# SCH_Linefollowerv1_2022-11-18.net
KiCad netlist of a schematic drawn in EasyEDA
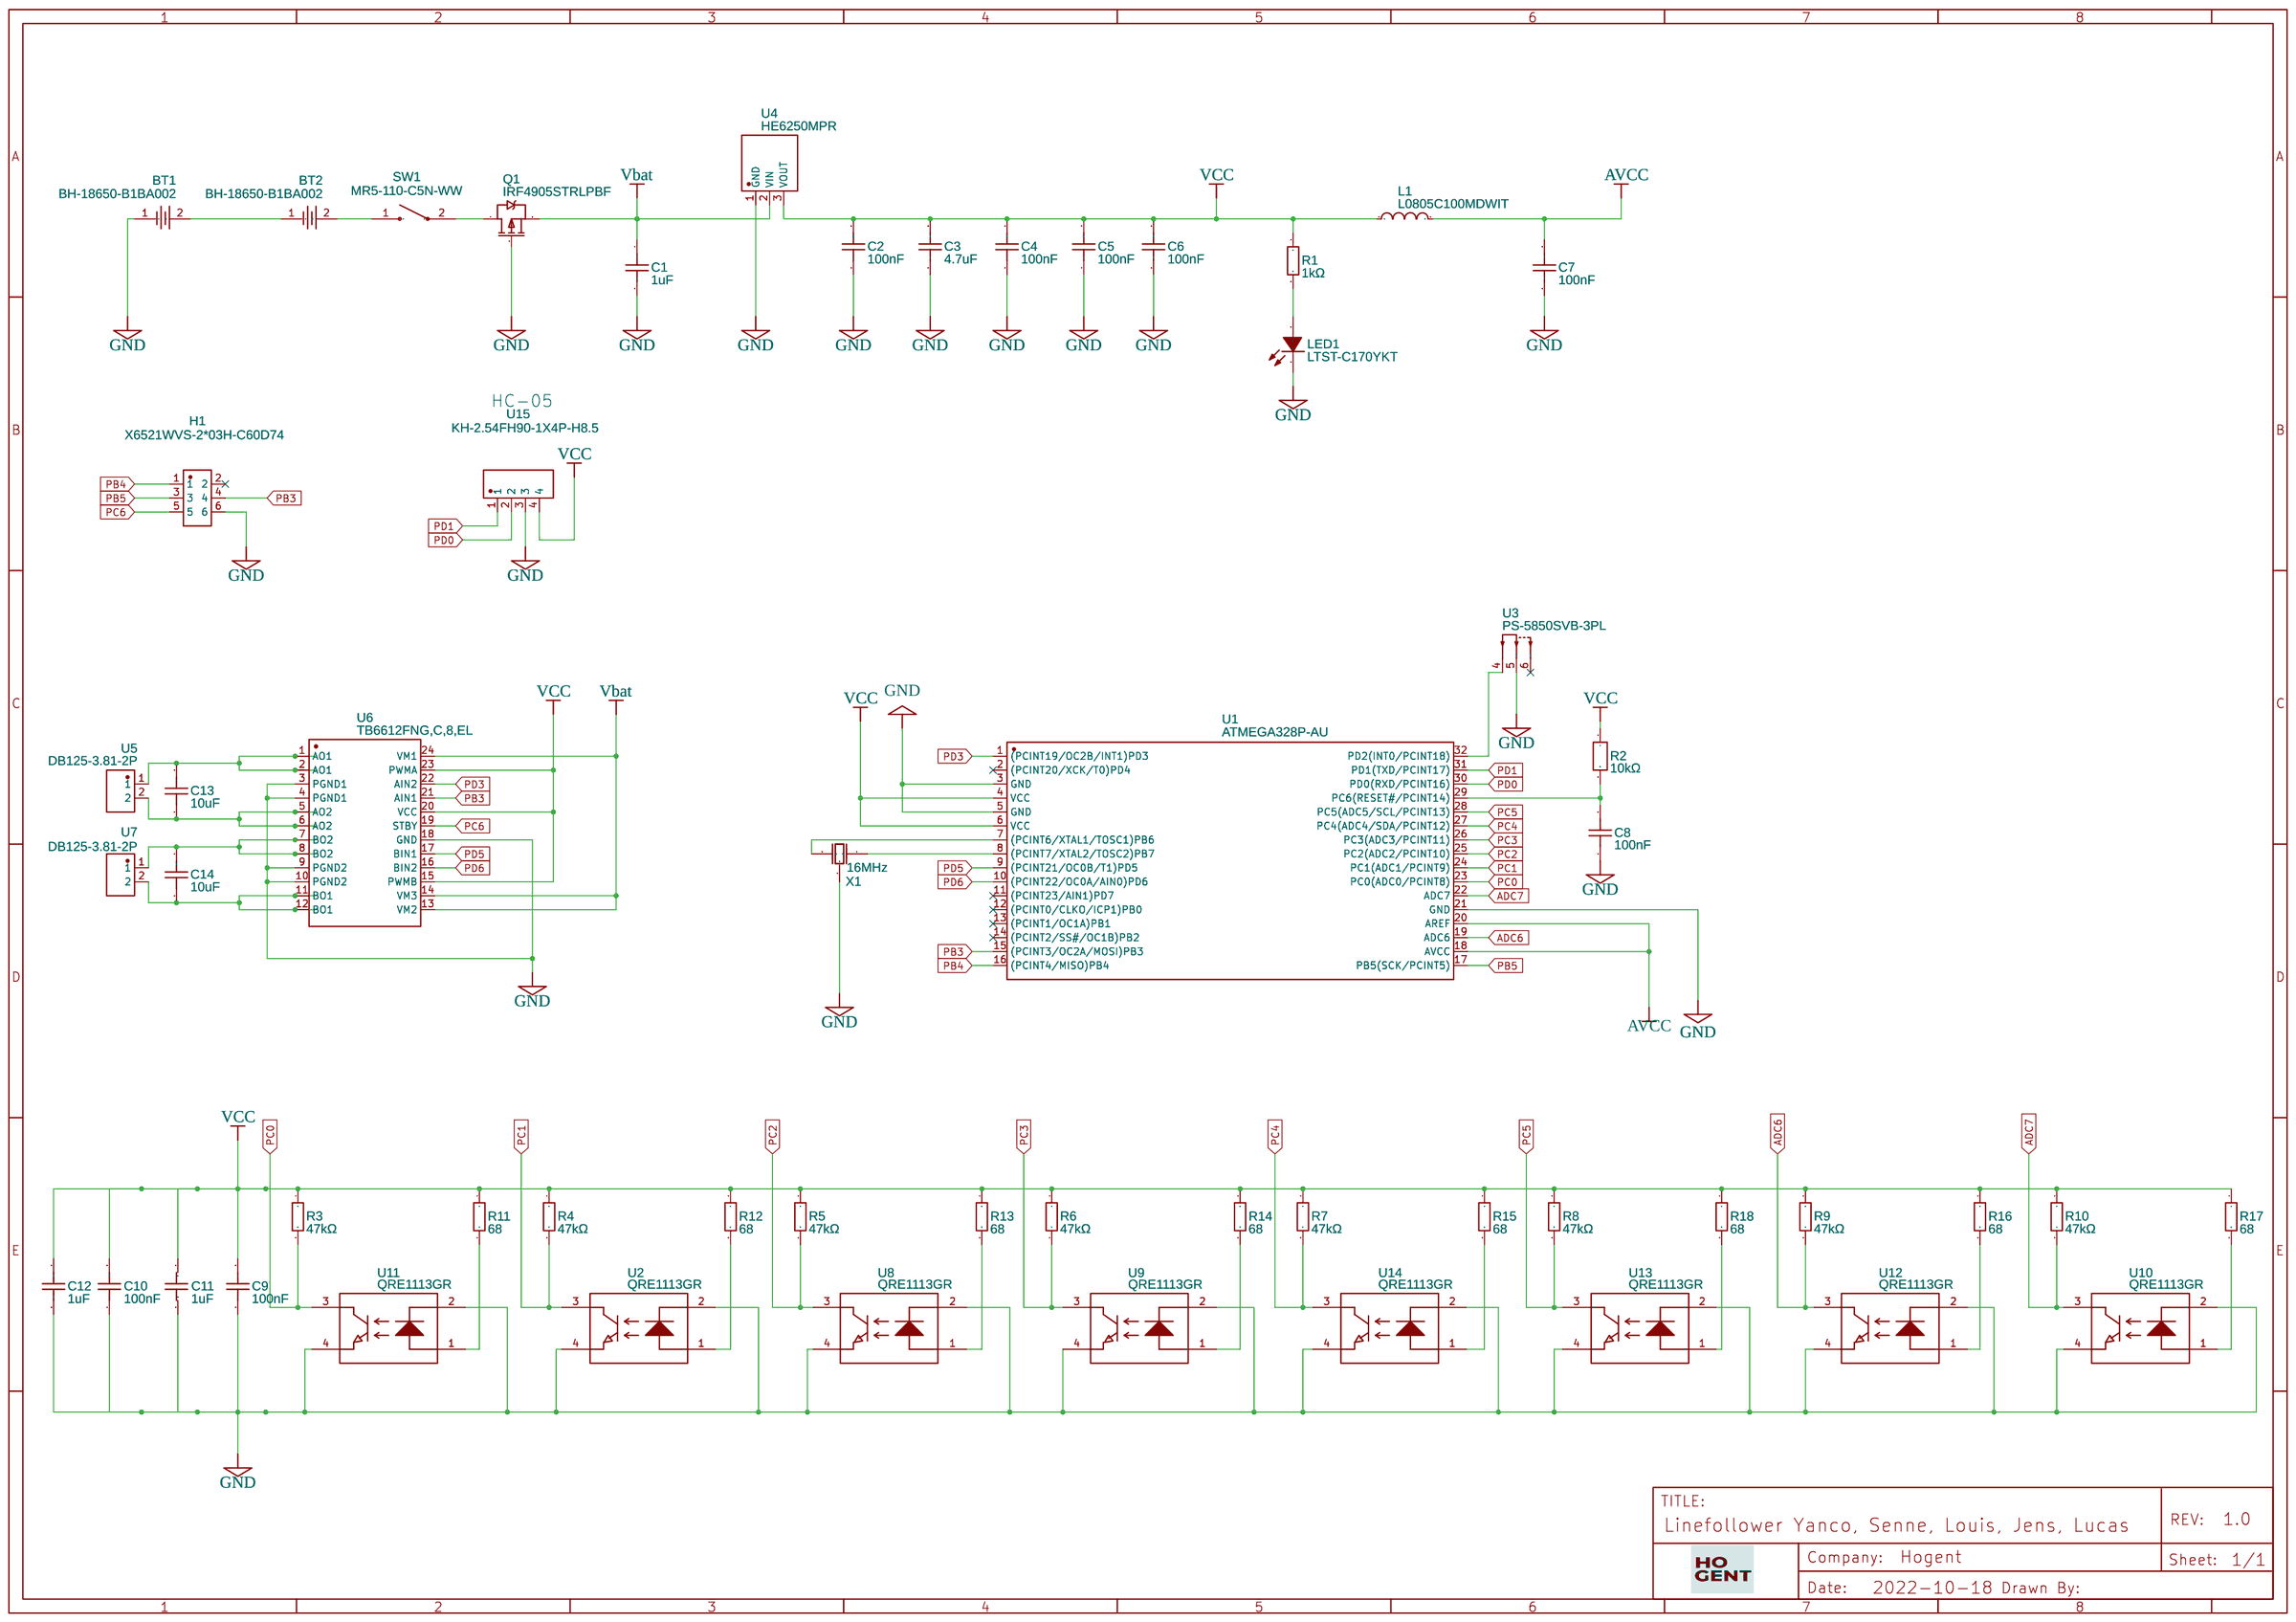
[diagram p0: schematic sheet]

(export (version "E")
  (design (tool "Eeschema 10.0.6"))
  (components
    (comp (ref "BT1")
      (value "BH-18650-B1BA002")
      (fields (field (name "BOM_Supplier Part") "C2988620"))
      (libsource (lib "") (part "BH-18650-B1BA002"))
    )
    (comp (ref "BT2")
      (value "BH-18650-B1BA002")
      (fields (field (name "BOM_Supplier Part") "C2988620"))
      (libsource (lib "") (part "BH-18650-B1BA002"))
    )
    (comp (ref "C1")
      (value "1uF")
      (fields
        (field (name "BOM_Manufacturer Part") "LMK212BJ105KD-T")
        (field (name "BOM_Supplier Part") "C92812")
      )
      (libsource (lib "") (part "LMK212BJ105KD-T_1"))
    )
    (comp (ref "C2")
      (value "100nF")
      (fields
        (field (name "BOM_Manufacturer Part") "LMK212SD104KG-T")
        (field (name "BOM_Supplier Part") "C386062")
      )
      (libsource (lib "") (part "LMK212SD104KG-T"))
    )
    (comp (ref "C3")
      (value "4.7uF")
      (fields
        (field (name "BOM_Manufacturer Part") "GCM21BC71A475KA73L")
        (field (name "BOM_Supplier Part") "C126583")
      )
      (libsource (lib "") (part "GCM21BC71A475KA73L"))
    )
    (comp (ref "C4")
      (value "100nF")
      (fields
        (field (name "BOM_Manufacturer Part") "LMK212SD104KG-T")
        (field (name "BOM_Supplier Part") "C386062")
      )
      (libsource (lib "") (part "LMK212SD104KG-T"))
    )
    (comp (ref "C5")
      (value "100nF")
      (fields
        (field (name "BOM_Manufacturer Part") "LMK212SD104KG-T")
        (field (name "BOM_Supplier Part") "C386062")
      )
      (libsource (lib "") (part "LMK212SD104KG-T"))
    )
    (comp (ref "C6")
      (value "100nF")
      (fields
        (field (name "BOM_Manufacturer Part") "LMK212SD104KG-T")
        (field (name "BOM_Supplier Part") "C386062")
      )
      (libsource (lib "") (part "LMK212SD104KG-T"))
    )
    (comp (ref "C7")
      (value "100nF")
      (fields
        (field (name "BOM_Manufacturer Part") "LMK212SD104KG-T")
        (field (name "BOM_Supplier Part") "C386062")
      )
      (libsource (lib "") (part "LMK212SD104KG-T"))
    )
    (comp (ref "C8")
      (value "100nF")
      (fields
        (field (name "BOM_Manufacturer Part") "LMK212SD104KG-T")
        (field (name "BOM_Supplier Part") "C386062")
      )
      (libsource (lib "") (part "LMK212SD104KG-T"))
    )
    (comp (ref "C9")
      (value "100nF")
      (fields
        (field (name "BOM_Manufacturer Part") "LMK212SD104KG-T")
        (field (name "BOM_Supplier Part") "C386062")
      )
      (libsource (lib "") (part "LMK212SD104KG-T"))
    )
    (comp (ref "C10")
      (value "100nF")
      (fields
        (field (name "BOM_Manufacturer Part") "LMK212SD104KG-T")
        (field (name "BOM_Supplier Part") "C386062")
      )
      (libsource (lib "") (part "LMK212SD104KG-T"))
    )
    (comp (ref "C11")
      (value "1uF")
      (fields
        (field (name "BOM_Manufacturer Part") "LMK212BJ105KD-T")
        (field (name "BOM_Supplier Part") "C92812")
      )
      (libsource (lib "") (part "LMK212BJ105KD-T"))
    )
    (comp (ref "C12")
      (value "1uF")
      (fields
        (field (name "BOM_Manufacturer Part") "LMK212BJ105KD-T")
        (field (name "BOM_Supplier Part") "C92812")
      )
      (libsource (lib "") (part "LMK212BJ105KD-T_1"))
    )
    (comp (ref "C13")
      (value "10uF")
      (fields
        (field (name "BOM_Manufacturer Part") "LMK212BJ106KD-T")
        (field (name "BOM_Supplier Part") "C89143")
      )
      (libsource (lib "") (part "LMK212BJ106KD-T"))
    )
    (comp (ref "C14")
      (value "10uF")
      (fields
        (field (name "BOM_Manufacturer Part") "LMK212BJ106KD-T")
        (field (name "BOM_Supplier Part") "C89143")
      )
      (libsource (lib "") (part "LMK212BJ106KD-T"))
    )
    (comp (ref "H1")
      (value "X6521WVS-2*03H-C60D74")
      (fields (field (name "BOM_Supplier Part") "C780054"))
      (libsource (lib "") (part "X6521WVS-2*03H-C60D74"))
    )
    (comp (ref "L1")
      (value "L0805C100MDWIT")
      (fields (field (name "BOM_Supplier Part") "C696787"))
      (libsource (lib "") (part "L0805C100MDWIT"))
    )
    (comp (ref "LED1")
      (value "LTST-C170YKT")
      (fields (field (name "BOM_Supplier Part") "C125092"))
      (libsource (lib "") (part "LTST-C170YKT"))
    )
    (comp (ref "Q1")
      (value "IRF4905STRLPBF")
      (fields (field (name "BOM_Supplier Part") "C2620"))
      (libsource (lib "") (part "IRF4905STRLPBF"))
    )
    (comp (ref "R1")
      (value "1kΩ")
      (fields
        (field (name "BOM_Manufacturer Part") "ARG05BTC1001")
        (field (name "BOM_Supplier Part") "C309081")
      )
      (libsource (lib "") (part "ARG05BTC1001"))
    )
    (comp (ref "R2")
      (value "10kΩ")
      (fields
        (field (name "BOM_Manufacturer Part") "ARG05BTC1002")
        (field (name "BOM_Supplier Part") "C406725")
      )
      (libsource (lib "") (part "ARG05BTC1002"))
    )
    (comp (ref "R3")
      (value "47kΩ")
      (fields
        (field (name "BOM_Manufacturer Part") "AECR0805F47K0K9")
        (field (name "BOM_Supplier Part") "C328397")
      )
      (libsource (lib "") (part "AECR0805F47K0K9"))
    )
    (comp (ref "R4")
      (value "47kΩ")
      (fields
        (field (name "BOM_Manufacturer Part") "AECR0805F47K0K9")
        (field (name "BOM_Supplier Part") "C328397")
      )
      (libsource (lib "") (part "AECR0805F47K0K9"))
    )
    (comp (ref "R5")
      (value "47kΩ")
      (fields
        (field (name "BOM_Manufacturer Part") "AECR0805F47K0K9")
        (field (name "BOM_Supplier Part") "C328397")
      )
      (libsource (lib "") (part "AECR0805F47K0K9"))
    )
    (comp (ref "R6")
      (value "47kΩ")
      (fields
        (field (name "BOM_Manufacturer Part") "AECR0805F47K0K9")
        (field (name "BOM_Supplier Part") "C328397")
      )
      (libsource (lib "") (part "AECR0805F47K0K9"))
    )
    (comp (ref "R7")
      (value "47kΩ")
      (fields
        (field (name "BOM_Manufacturer Part") "AECR0805F47K0K9")
        (field (name "BOM_Supplier Part") "C328397")
      )
      (libsource (lib "") (part "AECR0805F47K0K9"))
    )
    (comp (ref "R8")
      (value "47kΩ")
      (fields
        (field (name "BOM_Manufacturer Part") "AECR0805F47K0K9")
        (field (name "BOM_Supplier Part") "C328397")
      )
      (libsource (lib "") (part "AECR0805F47K0K9"))
    )
    (comp (ref "R9")
      (value "47kΩ")
      (fields
        (field (name "BOM_Manufacturer Part") "AECR0805F47K0K9")
        (field (name "BOM_Supplier Part") "C328397")
      )
      (libsource (lib "") (part "AECR0805F47K0K9"))
    )
    (comp (ref "R10")
      (value "47kΩ")
      (fields
        (field (name "BOM_Manufacturer Part") "AECR0805F47K0K9")
        (field (name "BOM_Supplier Part") "C328397")
      )
      (libsource (lib "") (part "AECR0805F47K0K9"))
    )
    (comp (ref "R11")
      (value "68")
      (fields
        (field (name "BOM_Manufacturer Part") "RC0805FR-0768RL")
        (field (name "BOM_Supplier Part") "C137498")
      )
      (libsource (lib "") (part "RC0805FR-0768RL"))
    )
    (comp (ref "R12")
      (value "68")
      (fields
        (field (name "BOM_Manufacturer Part") "RC0805FR-0768RL")
        (field (name "BOM_Supplier Part") "C137498")
      )
      (libsource (lib "") (part "RC0805FR-0768RL"))
    )
    (comp (ref "R13")
      (value "68")
      (fields
        (field (name "BOM_Manufacturer Part") "RC0805FR-0768RL")
        (field (name "BOM_Supplier Part") "C137498")
      )
      (libsource (lib "") (part "RC0805FR-0768RL"))
    )
    (comp (ref "R14")
      (value "68")
      (fields
        (field (name "BOM_Manufacturer Part") "RC0805FR-0768RL")
        (field (name "BOM_Supplier Part") "C137498")
      )
      (libsource (lib "") (part "RC0805FR-0768RL"))
    )
    (comp (ref "R15")
      (value "68")
      (fields
        (field (name "BOM_Manufacturer Part") "RC0805FR-0768RL")
        (field (name "BOM_Supplier Part") "C137498")
      )
      (libsource (lib "") (part "RC0805FR-0768RL"))
    )
    (comp (ref "R16")
      (value "68")
      (fields
        (field (name "BOM_Manufacturer Part") "RC0805FR-0768RL")
        (field (name "BOM_Supplier Part") "C137498")
      )
      (libsource (lib "") (part "RC0805FR-0768RL"))
    )
    (comp (ref "R17")
      (value "68")
      (fields
        (field (name "BOM_Manufacturer Part") "RC0805FR-0768RL")
        (field (name "BOM_Supplier Part") "C137498")
      )
      (libsource (lib "") (part "RC0805FR-0768RL"))
    )
    (comp (ref "R18")
      (value "68")
      (fields
        (field (name "BOM_Manufacturer Part") "RC0805FR-0768RL")
        (field (name "BOM_Supplier Part") "C137498")
      )
      (libsource (lib "") (part "RC0805FR-0768RL"))
    )
    (comp (ref "SW1")
      (value "MR5-110-C5N-WW")
      (fields (field (name "BOM_Supplier Part") "C2829507"))
      (libsource (lib "") (part "MR5-110-C5N-WW"))
    )
    (comp (ref "U1")
      (value "ATMEGA328P-AU")
      (fields (field (name "BOM_Supplier Part") "C14877"))
      (libsource (lib "") (part "ATMEGA328P-AU"))
    )
    (comp (ref "U2")
      (value "QRE1113GR")
      (fields (field (name "BOM_Supplier Part") "C232862"))
      (libsource (lib "") (part "QRE1113GR"))
    )
    (comp (ref "U3")
      (value "PS-5850SVB-3PL")
      (fields (field (name "BOM_Supplier Part") "C5159077"))
      (libsource (lib "") (part "PS-5850SVB-3PL"))
    )
    (comp (ref "U4")
      (value "HE6250MPR")
      (fields (field (name "BOM_Supplier Part") "C711940"))
      (libsource (lib "") (part "HE6250MPR"))
    )
    (comp (ref "U5")
      (value "DB125-3.81-2P")
      (fields (field (name "BOM_Supplier Part") "C395878"))
      (libsource (lib "") (part "DB125-3.81-2P"))
    )
    (comp (ref "U6")
      (value "TB6612FNG,C,8,EL")
      (fields (field (name "BOM_Supplier Part") "C141517"))
      (libsource (lib "") (part "Unknown_500_-570"))
    )
    (comp (ref "U7")
      (value "DB125-3.81-2P")
      (fields (field (name "BOM_Supplier Part") "C395878"))
      (libsource (lib "") (part "DB125-3.81-2P"))
    )
    (comp (ref "U8")
      (value "QRE1113GR")
      (fields (field (name "BOM_Supplier Part") "C232862"))
      (libsource (lib "") (part "QRE1113GR_4"))
    )
    (comp (ref "U9")
      (value "QRE1113GR")
      (fields (field (name "BOM_Supplier Part") "C232862"))
      (libsource (lib "") (part "QRE1113GR_2"))
    )
    (comp (ref "U10")
      (value "QRE1113GR")
      (fields (field (name "BOM_Supplier Part") "C232862"))
      (libsource (lib "") (part "QRE1113GR_6"))
    )
    (comp (ref "U11")
      (value "QRE1113GR")
      (fields (field (name "BOM_Supplier Part") "C232862"))
      (libsource (lib "") (part "QRE1113GR_6"))
    )
    (comp (ref "U12")
      (value "QRE1113GR")
      (fields (field (name "BOM_Supplier Part") "C232862"))
      (libsource (lib "") (part "QRE1113GR_5"))
    )
    (comp (ref "U13")
      (value "QRE1113GR")
      (fields (field (name "BOM_Supplier Part") "C232862"))
      (libsource (lib "") (part "QRE1113GR_1"))
    )
    (comp (ref "U14")
      (value "QRE1113GR")
      (fields (field (name "BOM_Supplier Part") "C232862"))
      (libsource (lib "") (part "QRE1113GR_3"))
    )
    (comp (ref "U15")
      (value "KH-2.54FH90-1X4P-H8.5")
      (fields (field (name "BOM_Supplier Part") "C2932680"))
      (libsource (lib "") (part "KH-2.54FH90-1X4P-H8.5"))
    )
    (comp (ref "X1")
      (value "16MHz")
      (fields
        (field (name "BOM_Manufacturer Part") "CSTNE16M0V53C000R0")
        (field (name "BOM_Supplier Part") "C882606")
      )
      (libsource (lib "") (part "CSTNE16M0V53C000R0"))
    )
  )
  (nets
    (net (code "1") (name "ADC6") (class "Default")
      (node (ref "R9") (pin "2") (pinfunction "2_2") (pintype "unspecified"))
      (node (ref "U1") (pin "19") (pinfunction "ADC6_19") (pintype "unspecified"))
      (node (ref "U12") (pin "3") (pinfunction "3_3") (pintype "input"))
    )
    (net (code "2") (name "ADC7") (class "Default")
      (node (ref "R10") (pin "2") (pinfunction "2_2") (pintype "unspecified"))
      (node (ref "U1") (pin "22") (pinfunction "ADC7_22") (pintype "unspecified"))
      (node (ref "U10") (pin "3") (pinfunction "3_3") (pintype "input"))
    )
    (net (code "3") (name "AVCC") (class "Default")
      (node (ref "C7") (pin "2") (pinfunction "2_2") (pintype "unspecified"))
      (node (ref "L1") (pin "2") (pinfunction "2_2") (pintype "unspecified"))
      (node (ref "U1") (pin "18") (pinfunction "AVCC_18") (pintype "unspecified"))
      (node (ref "U1") (pin "20") (pinfunction "AREF_20") (pintype "unspecified"))
    )
    (net (code "4") (name "GND") (class "Default")
      (node (ref "BT1") (pin "1") (pinfunction "1_1") (pintype "input"))
      (node (ref "C1") (pin "2") (pinfunction "2_2") (pintype "unspecified"))
      (node (ref "C10") (pin "1") (pinfunction "1_1") (pintype "unspecified"))
      (node (ref "C11") (pin "2") (pinfunction "2_2") (pintype "unspecified"))
      (node (ref "C12") (pin "2") (pinfunction "2_2") (pintype "unspecified"))
      (node (ref "C2") (pin "1") (pinfunction "1_1") (pintype "unspecified"))
      (node (ref "C3") (pin "1") (pinfunction "1_1") (pintype "unspecified"))
      (node (ref "C4") (pin "1") (pinfunction "1_1") (pintype "unspecified"))
      (node (ref "C5") (pin "1") (pinfunction "1_1") (pintype "unspecified"))
      (node (ref "C6") (pin "1") (pinfunction "1_1") (pintype "unspecified"))
      (node (ref "C7") (pin "1") (pinfunction "1_1") (pintype "unspecified"))
      (node (ref "C8") (pin "1") (pinfunction "1_1") (pintype "unspecified"))
      (node (ref "C9") (pin "1") (pinfunction "1_1") (pintype "unspecified"))
      (node (ref "H1") (pin "6") (pinfunction "6_6") (pintype "unspecified"))
      (node (ref "LED1") (pin "1") (pinfunction "1_1") (pintype "unspecified"))
      (node (ref "Q1") (pin "1") (pinfunction "G_1") (pintype "unspecified"))
      (node (ref "U1") (pin "21") (pinfunction "GND_21") (pintype "unspecified"))
      (node (ref "U1") (pin "3") (pinfunction "GND_3") (pintype "unspecified"))
      (node (ref "U1") (pin "5") (pinfunction "GND_5") (pintype "unspecified"))
      (node (ref "U10") (pin "2") (pinfunction "2_2") (pintype "input"))
      (node (ref "U10") (pin "4") (pinfunction "4_4") (pintype "input"))
      (node (ref "U11") (pin "2") (pinfunction "2_2") (pintype "input"))
      (node (ref "U11") (pin "4") (pinfunction "4_4") (pintype "input"))
      (node (ref "U12") (pin "2") (pinfunction "2_2") (pintype "input"))
      (node (ref "U12") (pin "4") (pinfunction "4_4") (pintype "input"))
      (node (ref "U13") (pin "2") (pinfunction "2_2") (pintype "input"))
      (node (ref "U13") (pin "4") (pinfunction "4_4") (pintype "input"))
      (node (ref "U14") (pin "2") (pinfunction "2_2") (pintype "input"))
      (node (ref "U14") (pin "4") (pinfunction "4_4") (pintype "input"))
      (node (ref "U15") (pin "3") (pinfunction "3_3") (pintype "unspecified"))
      (node (ref "U2") (pin "2") (pinfunction "2_2") (pintype "input"))
      (node (ref "U2") (pin "4") (pinfunction "4_4") (pintype "input"))
      (node (ref "U3") (pin "5") (pinfunction "5_5") (pintype "unspecified"))
      (node (ref "U4") (pin "1") (pinfunction "GND_1") (pintype "unspecified"))
      (node (ref "U6") (pin "10") (pinfunction "PGND2_10") (pintype "unspecified"))
      (node (ref "U6") (pin "18") (pinfunction "GND_18") (pintype "unspecified"))
      (node (ref "U6") (pin "3") (pinfunction "PGND1_3") (pintype "unspecified"))
      (node (ref "U6") (pin "4") (pinfunction "PGND1_4") (pintype "unspecified"))
      (node (ref "U6") (pin "9") (pinfunction "PGND2_9") (pintype "unspecified"))
      (node (ref "U8") (pin "2") (pinfunction "2_2") (pintype "input"))
      (node (ref "U8") (pin "4") (pinfunction "4_4") (pintype "input"))
      (node (ref "U9") (pin "2") (pinfunction "2_2") (pintype "input"))
      (node (ref "U9") (pin "4") (pinfunction "4_4") (pintype "input"))
      (node (ref "X1") (pin "2") (pinfunction "GND_2") (pintype "input"))
    )
    (net (code "5") (name "Net-(BT1-Pad2)") (class "Default")
      (node (ref "BT1") (pin "2") (pinfunction "2_2") (pintype "input"))
      (node (ref "BT2") (pin "1") (pinfunction "1_1") (pintype "input"))
    )
    (net (code "6") (name "Net-(BT2-Pad2)") (class "Default")
      (node (ref "BT2") (pin "2") (pinfunction "2_2") (pintype "input"))
      (node (ref "SW1") (pin "1") (pinfunction "1_1") (pintype "unspecified"))
    )
    (net (code "7") (name "Net-(C13-Pad1)") (class "Default")
      (node (ref "C13") (pin "1") (pinfunction "1_1") (pintype "unspecified"))
      (node (ref "U5") (pin "2") (pinfunction "2_2") (pintype "unspecified"))
      (node (ref "U6") (pin "5") (pinfunction "AO2_5") (pintype "unspecified"))
      (node (ref "U6") (pin "6") (pinfunction "AO2_6") (pintype "unspecified"))
    )
    (net (code "8") (name "Net-(C13-Pad2)") (class "Default")
      (node (ref "C13") (pin "2") (pinfunction "2_2") (pintype "unspecified"))
      (node (ref "U5") (pin "1") (pinfunction "1_1") (pintype "unspecified"))
      (node (ref "U6") (pin "1") (pinfunction "AO1_1") (pintype "unspecified"))
      (node (ref "U6") (pin "2") (pinfunction "AO1_2") (pintype "unspecified"))
    )
    (net (code "9") (name "Net-(C14-Pad1)") (class "Default")
      (node (ref "C14") (pin "1") (pinfunction "1_1") (pintype "unspecified"))
      (node (ref "U6") (pin "11") (pinfunction "BO1_11") (pintype "unspecified"))
      (node (ref "U6") (pin "12") (pinfunction "BO1_12") (pintype "unspecified"))
      (node (ref "U7") (pin "2") (pinfunction "2_2") (pintype "unspecified"))
    )
    (net (code "10") (name "Net-(C14-Pad2)") (class "Default")
      (node (ref "C14") (pin "2") (pinfunction "2_2") (pintype "unspecified"))
      (node (ref "U6") (pin "7") (pinfunction "BO2_7") (pintype "unspecified"))
      (node (ref "U6") (pin "8") (pinfunction "BO2_8") (pintype "unspecified"))
      (node (ref "U7") (pin "1") (pinfunction "1_1") (pintype "unspecified"))
    )
    (net (code "11") (name "Net-(LED1-Pad2)") (class "Default")
      (node (ref "LED1") (pin "2") (pinfunction "2_2") (pintype "unspecified"))
      (node (ref "R1") (pin "2") (pinfunction "2_2") (pintype "unspecified"))
    )
    (net (code "12") (name "Net-(Q1-D)") (class "Default")
      (node (ref "Q1") (pin "4") (pinfunction "D_4") (pintype "unspecified"))
      (node (ref "SW1") (pin "2") (pinfunction "2_2") (pintype "unspecified"))
    )
    (net (code "13") (name "Net-(R11-Pad2)") (class "Default")
      (node (ref "R11") (pin "2") (pinfunction "2_2") (pintype "input"))
      (node (ref "U11") (pin "1") (pinfunction "1_1") (pintype "input"))
    )
    (net (code "14") (name "Net-(R12-Pad2)") (class "Default")
      (node (ref "R12") (pin "2") (pinfunction "2_2") (pintype "input"))
      (node (ref "U2") (pin "1") (pinfunction "1_1") (pintype "input"))
    )
    (net (code "15") (name "Net-(R13-Pad2)") (class "Default")
      (node (ref "R13") (pin "2") (pinfunction "2_2") (pintype "input"))
      (node (ref "U8") (pin "1") (pinfunction "1_1") (pintype "input"))
    )
    (net (code "16") (name "Net-(R14-Pad2)") (class "Default")
      (node (ref "R14") (pin "2") (pinfunction "2_2") (pintype "input"))
      (node (ref "U9") (pin "1") (pinfunction "1_1") (pintype "input"))
    )
    (net (code "17") (name "Net-(R15-Pad2)") (class "Default")
      (node (ref "R15") (pin "2") (pinfunction "2_2") (pintype "input"))
      (node (ref "U14") (pin "1") (pinfunction "1_1") (pintype "input"))
    )
    (net (code "18") (name "Net-(R16-Pad2)") (class "Default")
      (node (ref "R16") (pin "2") (pinfunction "2_2") (pintype "input"))
      (node (ref "U12") (pin "1") (pinfunction "1_1") (pintype "input"))
    )
    (net (code "19") (name "Net-(R17-Pad2)") (class "Default")
      (node (ref "R17") (pin "2") (pinfunction "2_2") (pintype "input"))
      (node (ref "U10") (pin "1") (pinfunction "1_1") (pintype "input"))
    )
    (net (code "20") (name "Net-(R18-Pad2)") (class "Default")
      (node (ref "R18") (pin "2") (pinfunction "2_2") (pintype "input"))
      (node (ref "U13") (pin "1") (pinfunction "1_1") (pintype "input"))
    )
    (net (code "21") (name "Net-(U1-(PCINT6{slash}XTAL1{slash}TOSC1)PB6)") (class "Default")
      (node (ref "U1") (pin "7") (pinfunction "(PCINT6/XTAL1/TOSC1)PB6_7") (pintype "unspecified"))
      (node (ref "X1") (pin "3") (pinfunction "OSC2_3") (pintype "input"))
    )
    (net (code "22") (name "Net-(U1-(PCINT7{slash}XTAL2{slash}TOSC2)PB7)") (class "Default")
      (node (ref "U1") (pin "8") (pinfunction "(PCINT7/XTAL2/TOSC2)PB7_8") (pintype "unspecified"))
      (node (ref "X1") (pin "1") (pinfunction "OSC1_1") (pintype "input"))
    )
    (net (code "23") (name "Net-(U1-PC6(RESET#{slash}PCINT14))") (class "Default")
      (node (ref "C8") (pin "2") (pinfunction "2_2") (pintype "unspecified"))
      (node (ref "R2") (pin "2") (pinfunction "2_2") (pintype "unspecified"))
      (node (ref "U1") (pin "29") (pinfunction "PC6(RESET#/PCINT14)_29") (pintype "unspecified"))
    )
    (net (code "24") (name "Net-(U1-PD2(INT0{slash}PCINT18))") (class "Default")
      (node (ref "U1") (pin "32") (pinfunction "PD2(INT0/PCINT18)_32") (pintype "unspecified"))
      (node (ref "U3") (pin "4") (pinfunction "4_4") (pintype "unspecified"))
    )
    (net (code "25") (name "PB3") (class "Default")
      (node (ref "H1") (pin "4") (pinfunction "4_4") (pintype "unspecified"))
      (node (ref "U1") (pin "15") (pinfunction "(PCINT3/OC2A/MOSI)PB3_15") (pintype "unspecified"))
      (node (ref "U6") (pin "21") (pinfunction "AIN1_21") (pintype "unspecified"))
    )
    (net (code "26") (name "PB4") (class "Default")
      (node (ref "H1") (pin "1") (pinfunction "1_1") (pintype "unspecified"))
      (node (ref "U1") (pin "16") (pinfunction "(PCINT4/MISO)PB4_16") (pintype "unspecified"))
    )
    (net (code "27") (name "PB5") (class "Default")
      (node (ref "H1") (pin "3") (pinfunction "3_3") (pintype "unspecified"))
      (node (ref "U1") (pin "17") (pinfunction "PB5(SCK/PCINT5)_17") (pintype "unspecified"))
    )
    (net (code "28") (name "PC0") (class "Default")
      (node (ref "R3") (pin "2") (pinfunction "2_2") (pintype "unspecified"))
      (node (ref "U1") (pin "23") (pinfunction "PC0(ADC0/PCINT8)_23") (pintype "unspecified"))
      (node (ref "U11") (pin "3") (pinfunction "3_3") (pintype "input"))
    )
    (net (code "29") (name "PC1") (class "Default")
      (node (ref "R4") (pin "2") (pinfunction "2_2") (pintype "unspecified"))
      (node (ref "U1") (pin "24") (pinfunction "PC1(ADC1/PCINT9)_24") (pintype "unspecified"))
      (node (ref "U2") (pin "3") (pinfunction "3_3") (pintype "input"))
    )
    (net (code "30") (name "PC2") (class "Default")
      (node (ref "R5") (pin "2") (pinfunction "2_2") (pintype "unspecified"))
      (node (ref "U1") (pin "25") (pinfunction "PC2(ADC2/PCINT10)_25") (pintype "unspecified"))
      (node (ref "U8") (pin "3") (pinfunction "3_3") (pintype "input"))
    )
    (net (code "31") (name "PC3") (class "Default")
      (node (ref "R6") (pin "2") (pinfunction "2_2") (pintype "unspecified"))
      (node (ref "U1") (pin "26") (pinfunction "PC3(ADC3/PCINT11)_26") (pintype "unspecified"))
      (node (ref "U9") (pin "3") (pinfunction "3_3") (pintype "input"))
    )
    (net (code "32") (name "PC4") (class "Default")
      (node (ref "R7") (pin "2") (pinfunction "2_2") (pintype "unspecified"))
      (node (ref "U1") (pin "27") (pinfunction "PC4(ADC4/SDA/PCINT12)_27") (pintype "unspecified"))
      (node (ref "U14") (pin "3") (pinfunction "3_3") (pintype "input"))
    )
    (net (code "33") (name "PC5") (class "Default")
      (node (ref "R8") (pin "2") (pinfunction "2_2") (pintype "unspecified"))
      (node (ref "U1") (pin "28") (pinfunction "PC5(ADC5/SCL/PCINT13)_28") (pintype "unspecified"))
      (node (ref "U13") (pin "3") (pinfunction "3_3") (pintype "input"))
    )
    (net (code "34") (name "PC6") (class "Default")
      (node (ref "H1") (pin "5") (pinfunction "5_5") (pintype "unspecified"))
      (node (ref "U6") (pin "19") (pinfunction "STBY_19") (pintype "unspecified"))
    )
    (net (code "35") (name "PD0") (class "Default")
      (node (ref "U1") (pin "30") (pinfunction "PD0(RXD/PCINT16)_30") (pintype "unspecified"))
      (node (ref "U15") (pin "2") (pinfunction "2_2") (pintype "unspecified"))
    )
    (net (code "36") (name "PD1") (class "Default")
      (node (ref "U1") (pin "31") (pinfunction "PD1(TXD/PCINT17)_31") (pintype "unspecified"))
      (node (ref "U15") (pin "1") (pinfunction "1_1") (pintype "unspecified"))
    )
    (net (code "37") (name "PD3") (class "Default")
      (node (ref "U1") (pin "1") (pinfunction "(PCINT19/OC2B/INT1)PD3_1") (pintype "unspecified"))
      (node (ref "U6") (pin "22") (pinfunction "AIN2_22") (pintype "unspecified"))
    )
    (net (code "38") (name "PD5") (class "Default")
      (node (ref "U1") (pin "9") (pinfunction "(PCINT21/OC0B/T1)PD5_9") (pintype "unspecified"))
      (node (ref "U6") (pin "17") (pinfunction "BIN1_17") (pintype "unspecified"))
    )
    (net (code "39") (name "PD6") (class "Default")
      (node (ref "U1") (pin "10") (pinfunction "(PCINT22/OC0A/AIN0)PD6_10") (pintype "unspecified"))
      (node (ref "U6") (pin "16") (pinfunction "BIN2_16") (pintype "unspecified"))
    )
    (net (code "40") (name "VCC") (class "Default")
      (node (ref "C10") (pin "2") (pinfunction "2_2") (pintype "unspecified"))
      (node (ref "C11") (pin "1") (pinfunction "1_1") (pintype "unspecified"))
      (node (ref "C12") (pin "1") (pinfunction "1_1") (pintype "unspecified"))
      (node (ref "C2") (pin "2") (pinfunction "2_2") (pintype "unspecified"))
      (node (ref "C3") (pin "2") (pinfunction "2_2") (pintype "unspecified"))
      (node (ref "C4") (pin "2") (pinfunction "2_2") (pintype "unspecified"))
      (node (ref "C5") (pin "2") (pinfunction "2_2") (pintype "unspecified"))
      (node (ref "C6") (pin "2") (pinfunction "2_2") (pintype "unspecified"))
      (node (ref "C9") (pin "2") (pinfunction "2_2") (pintype "unspecified"))
      (node (ref "L1") (pin "1") (pinfunction "1_1") (pintype "unspecified"))
      (node (ref "R1") (pin "1") (pinfunction "1_1") (pintype "unspecified"))
      (node (ref "R10") (pin "1") (pinfunction "1_1") (pintype "unspecified"))
      (node (ref "R11") (pin "1") (pinfunction "1_1") (pintype "input"))
      (node (ref "R12") (pin "1") (pinfunction "1_1") (pintype "input"))
      (node (ref "R13") (pin "1") (pinfunction "1_1") (pintype "input"))
      (node (ref "R14") (pin "1") (pinfunction "1_1") (pintype "input"))
      (node (ref "R15") (pin "1") (pinfunction "1_1") (pintype "input"))
      (node (ref "R16") (pin "1") (pinfunction "1_1") (pintype "input"))
      (node (ref "R17") (pin "1") (pinfunction "1_1") (pintype "input"))
      (node (ref "R18") (pin "1") (pinfunction "1_1") (pintype "input"))
      (node (ref "R2") (pin "1") (pinfunction "1_1") (pintype "unspecified"))
      (node (ref "R3") (pin "1") (pinfunction "1_1") (pintype "unspecified"))
      (node (ref "R4") (pin "1") (pinfunction "1_1") (pintype "unspecified"))
      (node (ref "R5") (pin "1") (pinfunction "1_1") (pintype "unspecified"))
      (node (ref "R6") (pin "1") (pinfunction "1_1") (pintype "unspecified"))
      (node (ref "R7") (pin "1") (pinfunction "1_1") (pintype "unspecified"))
      (node (ref "R8") (pin "1") (pinfunction "1_1") (pintype "unspecified"))
      (node (ref "R9") (pin "1") (pinfunction "1_1") (pintype "unspecified"))
      (node (ref "U1") (pin "4") (pinfunction "VCC_4") (pintype "unspecified"))
      (node (ref "U1") (pin "6") (pinfunction "VCC_6") (pintype "unspecified"))
      (node (ref "U15") (pin "4") (pinfunction "4_4") (pintype "unspecified"))
      (node (ref "U4") (pin "3") (pinfunction "VOUT_3") (pintype "unspecified"))
      (node (ref "U6") (pin "15") (pinfunction "PWMB_15") (pintype "unspecified"))
      (node (ref "U6") (pin "20") (pinfunction "VCC_20") (pintype "unspecified"))
      (node (ref "U6") (pin "23") (pinfunction "PWMA_23") (pintype "unspecified"))
    )
    (net (code "41") (name "Vbat") (class "Default")
      (node (ref "C1") (pin "1") (pinfunction "1_1") (pintype "unspecified"))
      (node (ref "Q1") (pin "3") (pinfunction "S_3") (pintype "unspecified"))
      (node (ref "U4") (pin "2") (pinfunction "VIN_2") (pintype "unspecified"))
      (node (ref "U6") (pin "13") (pinfunction "VM2_13") (pintype "unspecified"))
      (node (ref "U6") (pin "14") (pinfunction "VM3_14") (pintype "unspecified"))
      (node (ref "U6") (pin "24") (pinfunction "VM1_24") (pintype "unspecified"))
    )
    (net (code "42") (name "unconnected-(H1-Pad2)") (class "Default")
      (node (ref "H1") (pin "2") (pinfunction "2_2") (pintype "unspecified+no_connect"))
    )
    (net (code "43") (name "unconnected-(U1-(PCINT0{slash}CLKO{slash}ICP1)PB0-Pad12)") (class "Default")
      (node (ref "U1") (pin "12") (pinfunction "(PCINT0/CLKO/ICP1)PB0_12") (pintype "unspecified+no_connect"))
    )
    (net (code "44") (name "unconnected-(U1-(PCINT1{slash}OC1A)PB1-Pad13)") (class "Default")
      (node (ref "U1") (pin "13") (pinfunction "(PCINT1/OC1A)PB1_13") (pintype "unspecified+no_connect"))
    )
    (net (code "45") (name "unconnected-(U1-(PCINT2{slash}SS#{slash}OC1B)PB2-Pad14)") (class "Default")
      (node (ref "U1") (pin "14") (pinfunction "(PCINT2/SS#/OC1B)PB2_14") (pintype "unspecified+no_connect"))
    )
    (net (code "46") (name "unconnected-(U1-(PCINT20{slash}XCK{slash}T0)PD4-Pad2)") (class "Default")
      (node (ref "U1") (pin "2") (pinfunction "(PCINT20/XCK/T0)PD4_2") (pintype "unspecified+no_connect"))
    )
    (net (code "47") (name "unconnected-(U1-(PCINT23{slash}AIN1)PD7-Pad11)") (class "Default")
      (node (ref "U1") (pin "11") (pinfunction "(PCINT23/AIN1)PD7_11") (pintype "unspecified+no_connect"))
    )
    (net (code "48") (name "unconnected-(U3-Pad6)") (class "Default")
      (node (ref "U3") (pin "6") (pinfunction "6_6") (pintype "unspecified+no_connect"))
    )
  )
)
